# 04_LMS7002M_Misc.net
KiCad netlist of a schematic drawn in Altium Designer
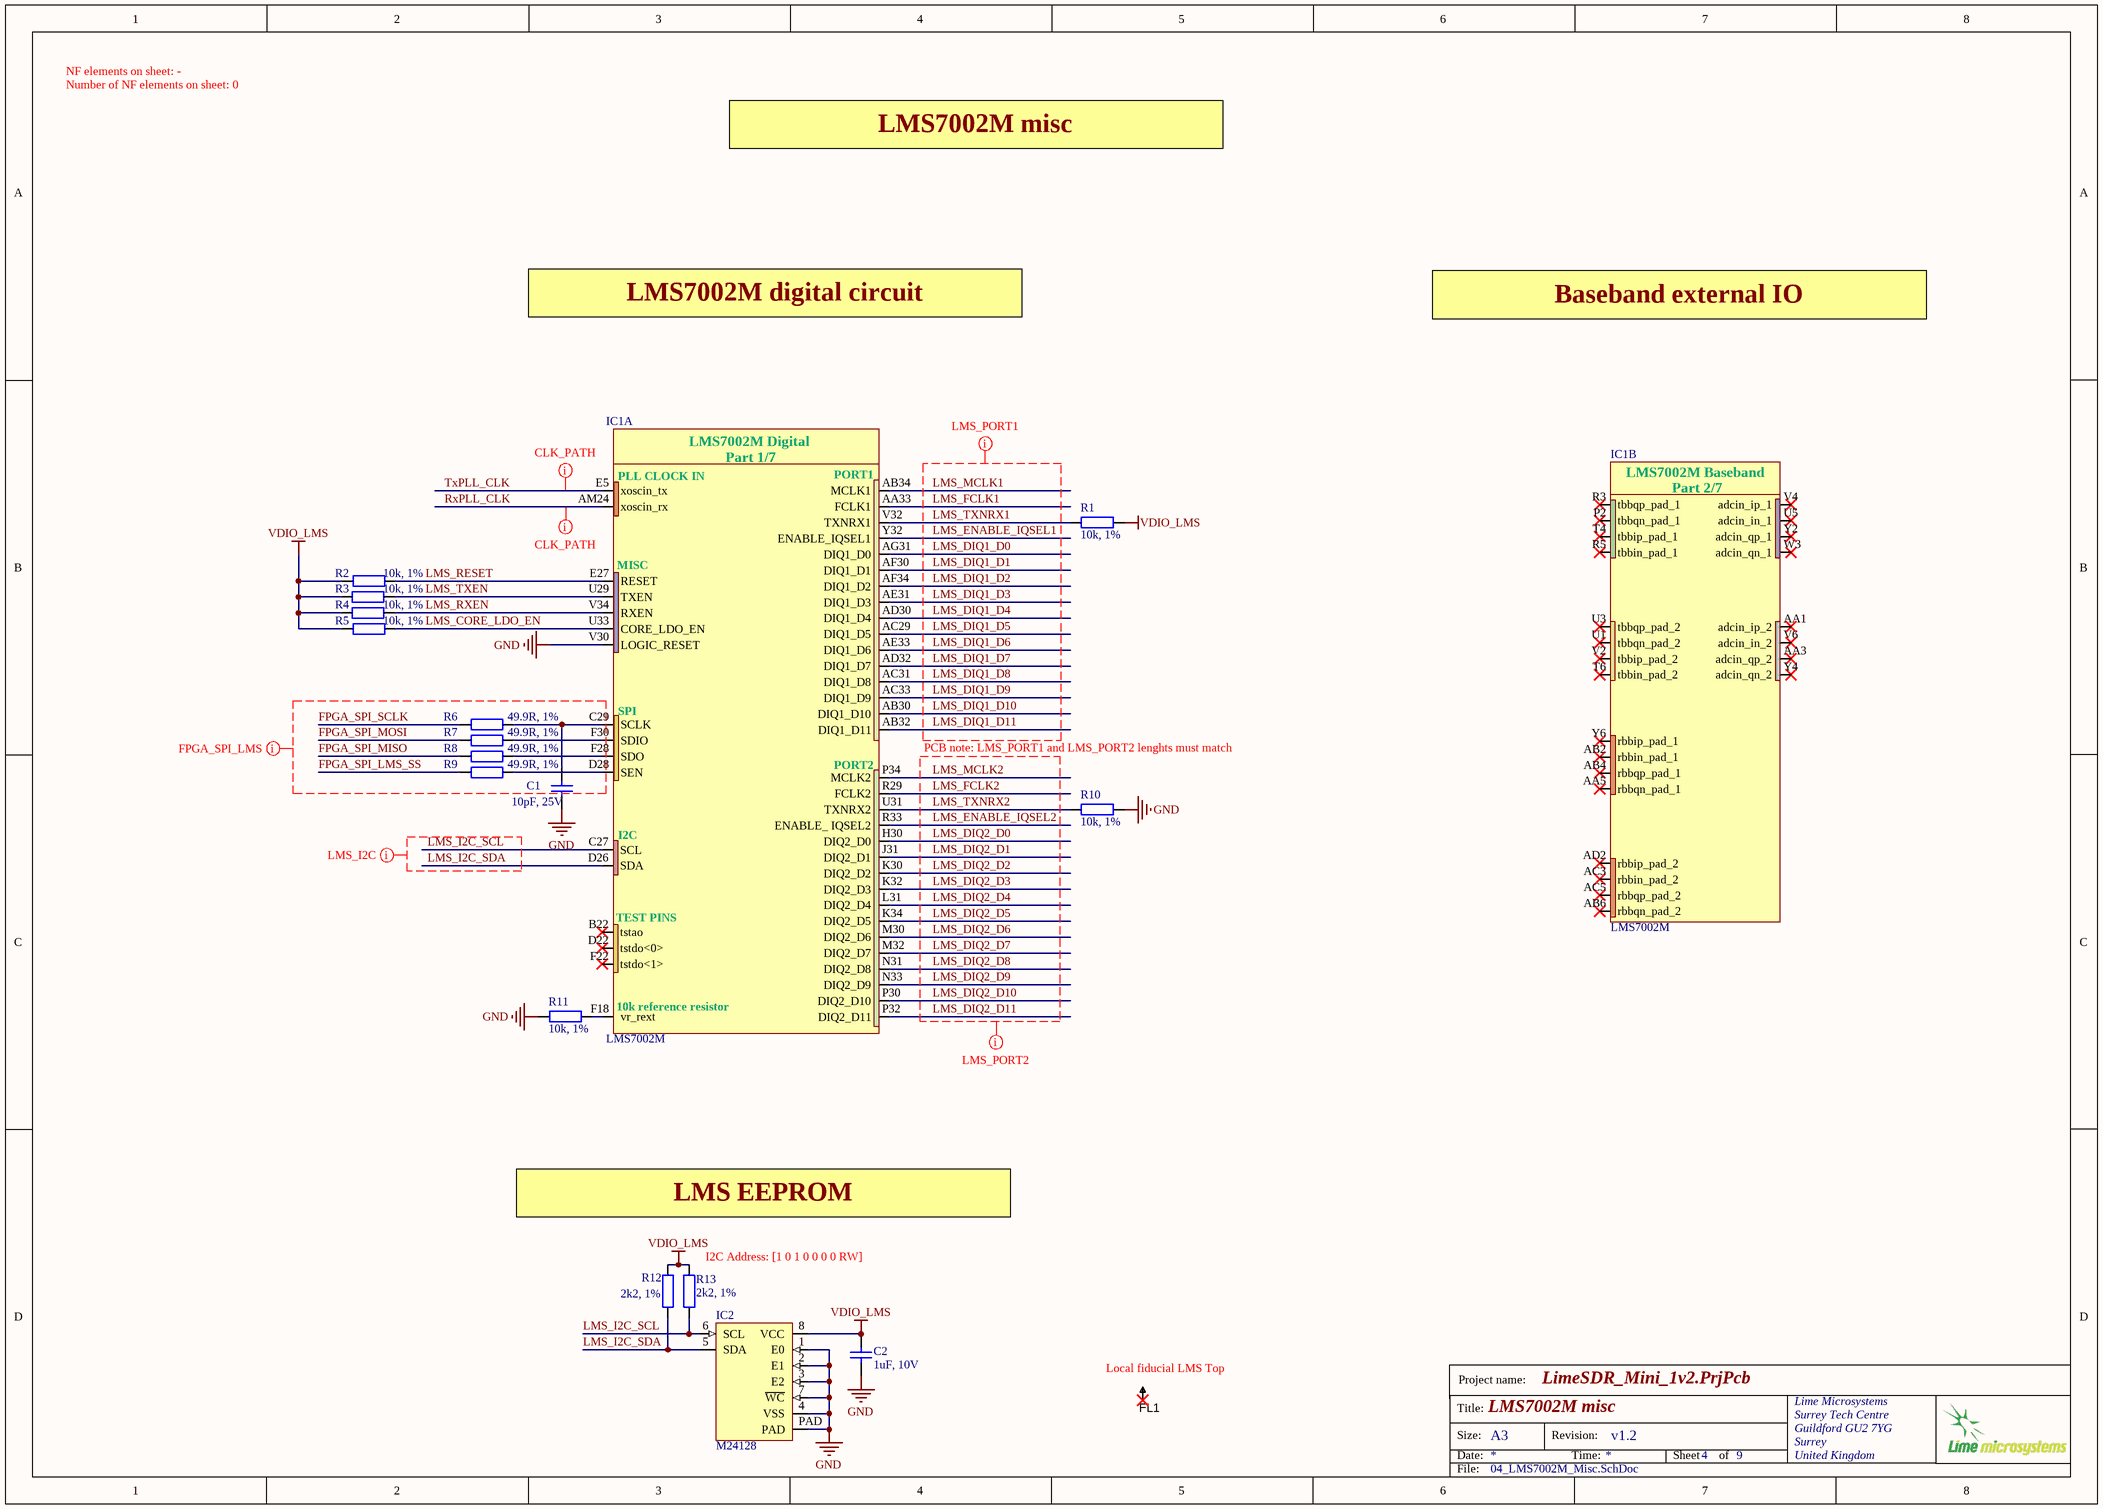
[diagram p0: 04_LMS7002M_Misc.SchDoc]

(export (version "E")
  (design (tool "Eeschema 10.0.6"))
  (components
    (comp (ref "C1")
      (value "10pF, 25V")
      (footprint "CAP0402")
      (fields (field (name "MANUFACTURER") "AVX"))
      (libsource (lib "LimeMicroAltiumLib_schLib") (part "Cap_0402"))
    )
    (comp (ref "C2")
      (value "1uF, 10V")
      (footprint "CAP0402")
      (fields (field (name "MANUFACTURER") "TDK"))
      (libsource (lib "LimeMicroAltiumLib_schLib") (part "Cap_0402"))
    )
    (comp (ref "FL1")
      (value "Fiducial")
      (footprint "Fiducial_local")
      (libsource (lib "VGTU_Altium_lib") (part "Fiducial"))
    )
    (comp (ref "IC1")
      (value "LMS7002M")
      (footprint "LMS7002M_v5")
      (description "Schematic symbol revision 3. Default footprint - 0.31mm pad")
      (fields (field (name "MANUFACTURER") "Lime Microsystems"))
      (libsource (lib "LimeMicroAltiumLib_schLib") (part "LMS7002Mr3"))
    )
    (comp (ref "IC2")
      (value "M24128")
      (footprint "M24128-DFMC6TG")
      (fields (field (name "MANUFACTURER") "STMicroelectronics"))
      (libsource (lib "LimeMicroAltiumLib_schLib") (part "M24128-DFMC6TG"))
    )
    (comp (ref "R1")
      (value "10k, 1%")
      (footprint "RES0402")
      (fields (field (name "MANUFACTURER") "Yageo") (field (name "TOLERANCE") "±1%"))
      (libsource (lib "LimeMicroAltiumLib_schLib") (part "Res_0402"))
    )
    (comp (ref "R2")
      (value "10k, 1%")
      (footprint "RES0402")
      (fields (field (name "MANUFACTURER") "Yageo") (field (name "TOLERANCE") "±1%"))
      (libsource (lib "LimeMicroAltiumLib_schLib") (part "Res_0402"))
    )
    (comp (ref "R3")
      (value "10k, 1%")
      (footprint "RES0402")
      (fields (field (name "MANUFACTURER") "Yageo") (field (name "TOLERANCE") "±1%"))
      (libsource (lib "LimeMicroAltiumLib_schLib") (part "Res_0402"))
    )
    (comp (ref "R4")
      (value "10k, 1%")
      (footprint "RES0402")
      (fields (field (name "MANUFACTURER") "Yageo") (field (name "TOLERANCE") "±1%"))
      (libsource (lib "LimeMicroAltiumLib_schLib") (part "Res_0402"))
    )
    (comp (ref "R5")
      (value "10k, 1%")
      (footprint "RES0402")
      (fields (field (name "MANUFACTURER") "Yageo") (field (name "TOLERANCE") "±1%"))
      (libsource (lib "LimeMicroAltiumLib_schLib") (part "Res_0402"))
    )
    (comp (ref "R6")
      (value "49.9R, 1%")
      (footprint "RES0402")
      (fields
        (field (name "TOLERANCE") "±1%")
        (field (name "MANUFACTURER") "Samsung Electro-Mechanics America, Inc.")
        (field (name "MANUFACTURER PART NUMBER") "RC1005F49R9CS")
      )
      (libsource (lib "LimeMicroAltiumLib_schLib") (part "Res_0402"))
    )
    (comp (ref "R7")
      (value "49.9R, 1%")
      (footprint "RES0402")
      (fields
        (field (name "TOLERANCE") "±1%")
        (field (name "MANUFACTURER") "Samsung Electro-Mechanics America, Inc.")
        (field (name "MANUFACTURER PART NUMBER") "RC1005F49R9CS")
      )
      (libsource (lib "LimeMicroAltiumLib_schLib") (part "Res_0402"))
    )
    (comp (ref "R8")
      (value "49.9R, 1%")
      (footprint "RES0402")
      (fields
        (field (name "TOLERANCE") "±1%")
        (field (name "MANUFACTURER") "Samsung Electro-Mechanics America, Inc.")
        (field (name "MANUFACTURER PART NUMBER") "RC1005F49R9CS")
      )
      (libsource (lib "LimeMicroAltiumLib_schLib") (part "Res_0402"))
    )
    (comp (ref "R9")
      (value "49.9R, 1%")
      (footprint "RES0402")
      (fields
        (field (name "TOLERANCE") "±1%")
        (field (name "MANUFACTURER") "Samsung Electro-Mechanics America, Inc.")
        (field (name "MANUFACTURER PART NUMBER") "RC1005F49R9CS")
      )
      (libsource (lib "LimeMicroAltiumLib_schLib") (part "Res_0402"))
    )
    (comp (ref "R10")
      (value "10k, 1%")
      (footprint "RES0402")
      (fields (field (name "MANUFACTURER") "Yageo") (field (name "TOLERANCE") "±1%"))
      (libsource (lib "LimeMicroAltiumLib_schLib") (part "Res_0402"))
    )
    (comp (ref "R11")
      (value "10k, 1%")
      (footprint "RES0402")
      (fields (field (name "MANUFACTURER") "Yageo") (field (name "TOLERANCE") "±1%"))
      (libsource (lib "LimeMicroAltiumLib_schLib") (part "Res_0402"))
    )
    (comp (ref "R12")
      (value "2k2, 1%")
      (footprint "RES0402")
      (fields (field (name "MANUFACTURER") "Stackpole Electronics Inc") (field (name "TOLERANCE") "±1%"))
      (libsource (lib "LimeMicroAltiumLib_schLib") (part "Res_0402"))
    )
    (comp (ref "R13")
      (value "2k2, 1%")
      (footprint "RES0402")
      (fields (field (name "MANUFACTURER") "Stackpole Electronics Inc") (field (name "TOLERANCE") "±1%"))
      (libsource (lib "LimeMicroAltiumLib_schLib") (part "Res_0402"))
    )
  )
  (nets
    (net (code "1") (name "/FPGA_SPI_LMS_SS") (class "Default")
      (node (ref "R9") (pin "2") (pinfunction "2_2") (pintype "passive"))
    )
    (net (code "2") (name "/FPGA_SPI_MISO") (class "Default")
      (node (ref "R8") (pin "2") (pinfunction "2_2") (pintype "passive"))
    )
    (net (code "3") (name "/FPGA_SPI_MOSI") (class "Default")
      (node (ref "R7") (pin "2") (pinfunction "2_2") (pintype "passive"))
    )
    (net (code "4") (name "/FPGA_SPI_SCLK") (class "Default")
      (node (ref "R6") (pin "2") (pinfunction "2_2") (pintype "passive"))
    )
    (net (code "5") (name "/LMS_CORE_LDO_EN") (class "Default")
      (node (ref "IC1") (pin "U33") (pinfunction "CORE_LDO_EN_U33") (pintype "passive"))
      (node (ref "R5") (pin "1") (pinfunction "1_1") (pintype "passive"))
    )
    (net (code "6") (name "/LMS_DIQ1_D0") (class "Default")
      (node (ref "IC1") (pin "AG31") (pinfunction "DIQ1_D0_AG31") (pintype "passive"))
    )
    (net (code "7") (name "/LMS_DIQ1_D1") (class "Default")
      (node (ref "IC1") (pin "AF30") (pinfunction "DIQ1_D1_AF30") (pintype "passive"))
    )
    (net (code "8") (name "/LMS_DIQ1_D2") (class "Default")
      (node (ref "IC1") (pin "AF34") (pinfunction "DIQ1_D2_AF34") (pintype "passive"))
    )
    (net (code "9") (name "/LMS_DIQ1_D3") (class "Default")
      (node (ref "IC1") (pin "AE31") (pinfunction "DIQ1_D3_AE31") (pintype "passive"))
    )
    (net (code "10") (name "/LMS_DIQ1_D4") (class "Default")
      (node (ref "IC1") (pin "AD30") (pinfunction "DIQ1_D4_AD30") (pintype "passive"))
    )
    (net (code "11") (name "/LMS_DIQ1_D5") (class "Default")
      (node (ref "IC1") (pin "AC29") (pinfunction "DIQ1_D5_AC29") (pintype "passive"))
    )
    (net (code "12") (name "/LMS_DIQ1_D6") (class "Default")
      (node (ref "IC1") (pin "AE33") (pinfunction "DIQ1_D6_AE33") (pintype "passive"))
    )
    (net (code "13") (name "/LMS_DIQ1_D7") (class "Default")
      (node (ref "IC1") (pin "AD32") (pinfunction "DIQ1_D7_AD32") (pintype "passive"))
    )
    (net (code "14") (name "/LMS_DIQ1_D8") (class "Default")
      (node (ref "IC1") (pin "AC31") (pinfunction "DIQ1_D8_AC31") (pintype "passive"))
    )
    (net (code "15") (name "/LMS_DIQ1_D9") (class "Default")
      (node (ref "IC1") (pin "AC33") (pinfunction "DIQ1_D9_AC33") (pintype "passive"))
    )
    (net (code "16") (name "/LMS_DIQ1_D10") (class "Default")
      (node (ref "IC1") (pin "AB30") (pinfunction "DIQ1_D10_AB30") (pintype "passive"))
    )
    (net (code "17") (name "/LMS_DIQ1_D11") (class "Default")
      (node (ref "IC1") (pin "AB32") (pinfunction "DIQ1_D11_AB32") (pintype "passive"))
    )
    (net (code "18") (name "/LMS_DIQ2_D0") (class "Default")
      (node (ref "IC1") (pin "H30") (pinfunction "DIQ2_D0_H30") (pintype "passive"))
    )
    (net (code "19") (name "/LMS_DIQ2_D1") (class "Default")
      (node (ref "IC1") (pin "J31") (pinfunction "DIQ2_D1_J31") (pintype "passive"))
    )
    (net (code "20") (name "/LMS_DIQ2_D2") (class "Default")
      (node (ref "IC1") (pin "K30") (pinfunction "DIQ2_D2_K30") (pintype "passive"))
    )
    (net (code "21") (name "/LMS_DIQ2_D3") (class "Default")
      (node (ref "IC1") (pin "K32") (pinfunction "DIQ2_D3_K32") (pintype "passive"))
    )
    (net (code "22") (name "/LMS_DIQ2_D4") (class "Default")
      (node (ref "IC1") (pin "L31") (pinfunction "DIQ2_D4_L31") (pintype "passive"))
    )
    (net (code "23") (name "/LMS_DIQ2_D5") (class "Default")
      (node (ref "IC1") (pin "K34") (pinfunction "DIQ2_D5_K34") (pintype "passive"))
    )
    (net (code "24") (name "/LMS_DIQ2_D6") (class "Default")
      (node (ref "IC1") (pin "M30") (pinfunction "DIQ2_D6_M30") (pintype "passive"))
    )
    (net (code "25") (name "/LMS_DIQ2_D7") (class "Default")
      (node (ref "IC1") (pin "M32") (pinfunction "DIQ2_D7_M32") (pintype "passive"))
    )
    (net (code "26") (name "/LMS_DIQ2_D8") (class "Default")
      (node (ref "IC1") (pin "N31") (pinfunction "DIQ2_D8_N31") (pintype "passive"))
    )
    (net (code "27") (name "/LMS_DIQ2_D9") (class "Default")
      (node (ref "IC1") (pin "N33") (pinfunction "DIQ2_D9_N33") (pintype "passive"))
    )
    (net (code "28") (name "/LMS_DIQ2_D10") (class "Default")
      (node (ref "IC1") (pin "P30") (pinfunction "DIQ2_D10_P30") (pintype "passive"))
    )
    (net (code "29") (name "/LMS_DIQ2_D11") (class "Default")
      (node (ref "IC1") (pin "P32") (pinfunction "DIQ2_D11_P32") (pintype "passive"))
    )
    (net (code "30") (name "/LMS_ENABLE_IQSEL1") (class "Default")
      (node (ref "IC1") (pin "Y32") (pinfunction "ENABLE_IQSEL1_Y32") (pintype "passive"))
    )
    (net (code "31") (name "/LMS_ENABLE_IQSEL2") (class "Default")
      (node (ref "IC1") (pin "R33") (pinfunction "ENABLE__IQSEL2_R33") (pintype "passive"))
    )
    (net (code "32") (name "/LMS_FCLK1") (class "Default")
      (node (ref "IC1") (pin "AA33") (pinfunction "FCLK1_AA33") (pintype "passive"))
    )
    (net (code "33") (name "/LMS_FCLK2") (class "Default")
      (node (ref "IC1") (pin "R29") (pinfunction "FCLK2_R29") (pintype "passive"))
    )
    (net (code "34") (name "/LMS_I2C_SCL") (class "Default")
      (node (ref "IC1") (pin "C27") (pinfunction "SCL_C27") (pintype "passive"))
      (node (ref "IC2") (pin "6") (pinfunction "SCL_6") (pintype "input"))
      (node (ref "R13") (pin "2") (pinfunction "2_2") (pintype "passive"))
    )
    (net (code "35") (name "/LMS_I2C_SDA") (class "Default")
      (node (ref "IC1") (pin "D26") (pinfunction "SDA_D26") (pintype "passive"))
      (node (ref "IC2") (pin "5") (pinfunction "SDA_5") (pintype "bidirectional"))
      (node (ref "R12") (pin "2") (pinfunction "2_2") (pintype "passive"))
    )
    (net (code "36") (name "/LMS_MCLK1") (class "Default")
      (node (ref "IC1") (pin "AB34") (pinfunction "MCLK1_AB34") (pintype "passive"))
    )
    (net (code "37") (name "/LMS_MCLK2") (class "Default")
      (node (ref "IC1") (pin "P34") (pinfunction "MCLK2_P34") (pintype "passive"))
    )
    (net (code "38") (name "/LMS_RESET") (class "Default")
      (node (ref "IC1") (pin "E27") (pinfunction "RESET_E27") (pintype "passive"))
      (node (ref "R2") (pin "1") (pinfunction "1_1") (pintype "passive"))
    )
    (net (code "39") (name "/LMS_RXEN") (class "Default")
      (node (ref "IC1") (pin "V34") (pinfunction "RXEN_V34") (pintype "passive"))
      (node (ref "R4") (pin "2") (pinfunction "2_2") (pintype "passive"))
    )
    (net (code "40") (name "/LMS_TXEN") (class "Default")
      (node (ref "IC1") (pin "U29") (pinfunction "TXEN_U29") (pintype "passive"))
      (node (ref "R3") (pin "2") (pinfunction "2_2") (pintype "passive"))
    )
    (net (code "41") (name "/LMS_TXNRX1") (class "Default")
      (node (ref "IC1") (pin "V32") (pinfunction "TXNRX1_V32") (pintype "passive"))
      (node (ref "R1") (pin "1") (pinfunction "1_1") (pintype "passive"))
    )
    (net (code "42") (name "/LMS_TXNRX2") (class "Default")
      (node (ref "IC1") (pin "U31") (pinfunction "TXNRX2_U31") (pintype "passive"))
      (node (ref "R10") (pin "1") (pinfunction "1_1") (pintype "passive"))
    )
    (net (code "43") (name "/RxPLL_CLK") (class "Default")
      (node (ref "IC1") (pin "AM24") (pinfunction "xoscin_rx_AM24") (pintype "passive"))
    )
    (net (code "44") (name "/TxPLL_CLK") (class "Default")
      (node (ref "IC1") (pin "E5") (pinfunction "xoscin_tx_E5") (pintype "passive"))
    )
    (net (code "45") (name "GND") (class "Default")
      (node (ref "C1") (pin "2") (pinfunction "2_2") (pintype "passive"))
      (node (ref "C2") (pin "2") (pinfunction "2_2") (pintype "passive"))
      (node (ref "IC1") (pin "V30") (pinfunction "LOGIC_RESET_V30") (pintype "passive"))
      (node (ref "IC2") (pin "1") (pinfunction "E0_1") (pintype "input"))
      (node (ref "IC2") (pin "2") (pinfunction "E1_2") (pintype "input"))
      (node (ref "IC2") (pin "3") (pinfunction "E2_3") (pintype "input"))
      (node (ref "IC2") (pin "4") (pinfunction "VSS_4") (pintype "power_in"))
      (node (ref "IC2") (pin "7") (pinfunction "~{WC}_7") (pintype "input"))
      (node (ref "IC2") (pin "PAD") (pinfunction "PAD_PAD") (pintype "power_in"))
      (node (ref "R10") (pin "2") (pinfunction "2_2") (pintype "passive"))
      (node (ref "R11") (pin "2") (pinfunction "2_2") (pintype "passive"))
    )
    (net (code "46") (name "Net-(IC1A-SCLK)") (class "Default")
      (node (ref "C1") (pin "1") (pinfunction "1_1") (pintype "passive"))
      (node (ref "IC1") (pin "C29") (pinfunction "SCLK_C29") (pintype "passive"))
      (node (ref "R6") (pin "1") (pinfunction "1_1") (pintype "passive"))
    )
    (net (code "47") (name "Net-(IC1A-SDIO)") (class "Default")
      (node (ref "IC1") (pin "F30") (pinfunction "SDIO_F30") (pintype "passive"))
      (node (ref "R7") (pin "1") (pinfunction "1_1") (pintype "passive"))
    )
    (net (code "48") (name "Net-(IC1A-SDO)") (class "Default")
      (node (ref "IC1") (pin "F28") (pinfunction "SDO_F28") (pintype "passive"))
      (node (ref "R8") (pin "1") (pinfunction "1_1") (pintype "passive"))
    )
    (net (code "49") (name "Net-(IC1A-SEN)") (class "Default")
      (node (ref "IC1") (pin "D28") (pinfunction "SEN_D28") (pintype "passive"))
      (node (ref "R9") (pin "1") (pinfunction "1_1") (pintype "passive"))
    )
    (net (code "50") (name "Net-(IC1A-vr_rext)") (class "Default")
      (node (ref "IC1") (pin "F18") (pinfunction "vr_rext_F18") (pintype "passive"))
      (node (ref "R11") (pin "1") (pinfunction "1_1") (pintype "passive"))
    )
    (net (code "51") (name "VDIO_LMS") (class "Default")
      (node (ref "C2") (pin "1") (pinfunction "1_1") (pintype "passive"))
      (node (ref "IC2") (pin "8") (pinfunction "VCC_8") (pintype "power_in"))
      (node (ref "R1") (pin "2") (pinfunction "2_2") (pintype "passive"))
      (node (ref "R12") (pin "1") (pinfunction "1_1") (pintype "passive"))
      (node (ref "R13") (pin "1") (pinfunction "1_1") (pintype "passive"))
      (node (ref "R2") (pin "2") (pinfunction "2_2") (pintype "passive"))
      (node (ref "R3") (pin "1") (pinfunction "1_1") (pintype "passive"))
      (node (ref "R4") (pin "1") (pinfunction "1_1") (pintype "passive"))
      (node (ref "R5") (pin "2") (pinfunction "2_2") (pintype "passive"))
    )
    (net (code "52") (name "unconnected-(FL1-Pad1)") (class "Default")
      (node (ref "FL1") (pin "1") (pintype "passive+no_connect"))
    )
    (net (code "53") (name "unconnected-(IC1A-tstao-PadB22)") (class "Default")
      (node (ref "IC1") (pin "B22") (pinfunction "tstao_B22") (pintype "passive+no_connect"))
    )
    (net (code "54") (name "unconnected-(IC1A-tstdo<0>-PadD22)") (class "Default")
      (node (ref "IC1") (pin "D22") (pinfunction "tstdo<0>_D22") (pintype "passive+no_connect"))
    )
    (net (code "55") (name "unconnected-(IC1A-tstdo<1>-PadF22)") (class "Default")
      (node (ref "IC1") (pin "F22") (pinfunction "tstdo<1>_F22") (pintype "passive+no_connect"))
    )
    (net (code "56") (name "unconnected-(IC1B-adcin_in_1-PadU5)") (class "Default")
      (node (ref "IC1") (pin "U5") (pinfunction "adcin_in_1_U5") (pintype "passive+no_connect"))
    )
    (net (code "57") (name "unconnected-(IC1B-adcin_in_2-PadV6)") (class "Default")
      (node (ref "IC1") (pin "V6") (pinfunction "adcin_in_2_V6") (pintype "passive+no_connect"))
    )
    (net (code "58") (name "unconnected-(IC1B-adcin_ip_1-PadV4)") (class "Default")
      (node (ref "IC1") (pin "V4") (pinfunction "adcin_ip_1_V4") (pintype "passive+no_connect"))
    )
    (net (code "59") (name "unconnected-(IC1B-adcin_ip_2-PadAA1)") (class "Default")
      (node (ref "IC1") (pin "AA1") (pinfunction "adcin_ip_2_AA1") (pintype "passive+no_connect"))
    )
    (net (code "60") (name "unconnected-(IC1B-adcin_qn_1-PadW3)") (class "Default")
      (node (ref "IC1") (pin "W3") (pinfunction "adcin_qn_1_W3") (pintype "passive+no_connect"))
    )
    (net (code "61") (name "unconnected-(IC1B-adcin_qn_2-PadY4)") (class "Default")
      (node (ref "IC1") (pin "Y4") (pinfunction "adcin_qn_2_Y4") (pintype "passive+no_connect"))
    )
    (net (code "62") (name "unconnected-(IC1B-adcin_qp_1-PadY2)") (class "Default")
      (node (ref "IC1") (pin "Y2") (pinfunction "adcin_qp_1_Y2") (pintype "passive+no_connect"))
    )
    (net (code "63") (name "unconnected-(IC1B-adcin_qp_2-PadAA3)") (class "Default")
      (node (ref "IC1") (pin "AA3") (pinfunction "adcin_qp_2_AA3") (pintype "passive+no_connect"))
    )
    (net (code "64") (name "unconnected-(IC1B-rbbin_pad_1-PadAB2)") (class "Default")
      (node (ref "IC1") (pin "AB2") (pinfunction "rbbin_pad_1_AB2") (pintype "passive+no_connect"))
    )
    (net (code "65") (name "unconnected-(IC1B-rbbin_pad_2-PadAC3)") (class "Default")
      (node (ref "IC1") (pin "AC3") (pinfunction "rbbin_pad_2_AC3") (pintype "passive+no_connect"))
    )
    (net (code "66") (name "unconnected-(IC1B-rbbip_pad_1-PadY6)") (class "Default")
      (node (ref "IC1") (pin "Y6") (pinfunction "rbbip_pad_1_Y6") (pintype "passive+no_connect"))
    )
    (net (code "67") (name "unconnected-(IC1B-rbbip_pad_2-PadAD2)") (class "Default")
      (node (ref "IC1") (pin "AD2") (pinfunction "rbbip_pad_2_AD2") (pintype "passive+no_connect"))
    )
    (net (code "68") (name "unconnected-(IC1B-rbbqn_pad_1-PadAA5)") (class "Default")
      (node (ref "IC1") (pin "AA5") (pinfunction "rbbqn_pad_1_AA5") (pintype "passive+no_connect"))
    )
    (net (code "69") (name "unconnected-(IC1B-rbbqn_pad_2-PadAB6)") (class "Default")
      (node (ref "IC1") (pin "AB6") (pinfunction "rbbqn_pad_2_AB6") (pintype "passive+no_connect"))
    )
    (net (code "70") (name "unconnected-(IC1B-rbbqp_pad_1-PadAB4)") (class "Default")
      (node (ref "IC1") (pin "AB4") (pinfunction "rbbqp_pad_1_AB4") (pintype "passive+no_connect"))
    )
    (net (code "71") (name "unconnected-(IC1B-rbbqp_pad_2-PadAC5)") (class "Default")
      (node (ref "IC1") (pin "AC5") (pinfunction "rbbqp_pad_2_AC5") (pintype "passive+no_connect"))
    )
    (net (code "72") (name "unconnected-(IC1B-tbbin_pad_1-PadR5)") (class "Default")
      (node (ref "IC1") (pin "R5") (pinfunction "tbbin_pad_1_R5") (pintype "passive+no_connect"))
    )
    (net (code "73") (name "unconnected-(IC1B-tbbin_pad_2-PadT6)") (class "Default")
      (node (ref "IC1") (pin "T6") (pinfunction "tbbin_pad_2_T6") (pintype "passive+no_connect"))
    )
    (net (code "74") (name "unconnected-(IC1B-tbbip_pad_1-PadT4)") (class "Default")
      (node (ref "IC1") (pin "T4") (pinfunction "tbbip_pad_1_T4") (pintype "passive+no_connect"))
    )
    (net (code "75") (name "unconnected-(IC1B-tbbip_pad_2-PadV2)") (class "Default")
      (node (ref "IC1") (pin "V2") (pinfunction "tbbip_pad_2_V2") (pintype "passive+no_connect"))
    )
    (net (code "76") (name "unconnected-(IC1B-tbbqn_pad_1-PadP2)") (class "Default")
      (node (ref "IC1") (pin "P2") (pinfunction "tbbqn_pad_1_P2") (pintype "passive+no_connect"))
    )
    (net (code "77") (name "unconnected-(IC1B-tbbqn_pad_2-PadU1)") (class "Default")
      (node (ref "IC1") (pin "U1") (pinfunction "tbbqn_pad_2_U1") (pintype "passive+no_connect"))
    )
    (net (code "78") (name "unconnected-(IC1B-tbbqp_pad_1-PadR3)") (class "Default")
      (node (ref "IC1") (pin "R3") (pinfunction "tbbqp_pad_1_R3") (pintype "passive+no_connect"))
    )
    (net (code "79") (name "unconnected-(IC1B-tbbqp_pad_2-PadU3)") (class "Default")
      (node (ref "IC1") (pin "U3") (pinfunction "tbbqp_pad_2_U3") (pintype "passive+no_connect"))
    )
  )
)
